# protoBoardLogic.net
KiCad netlist of a schematic drawn in EAGLE
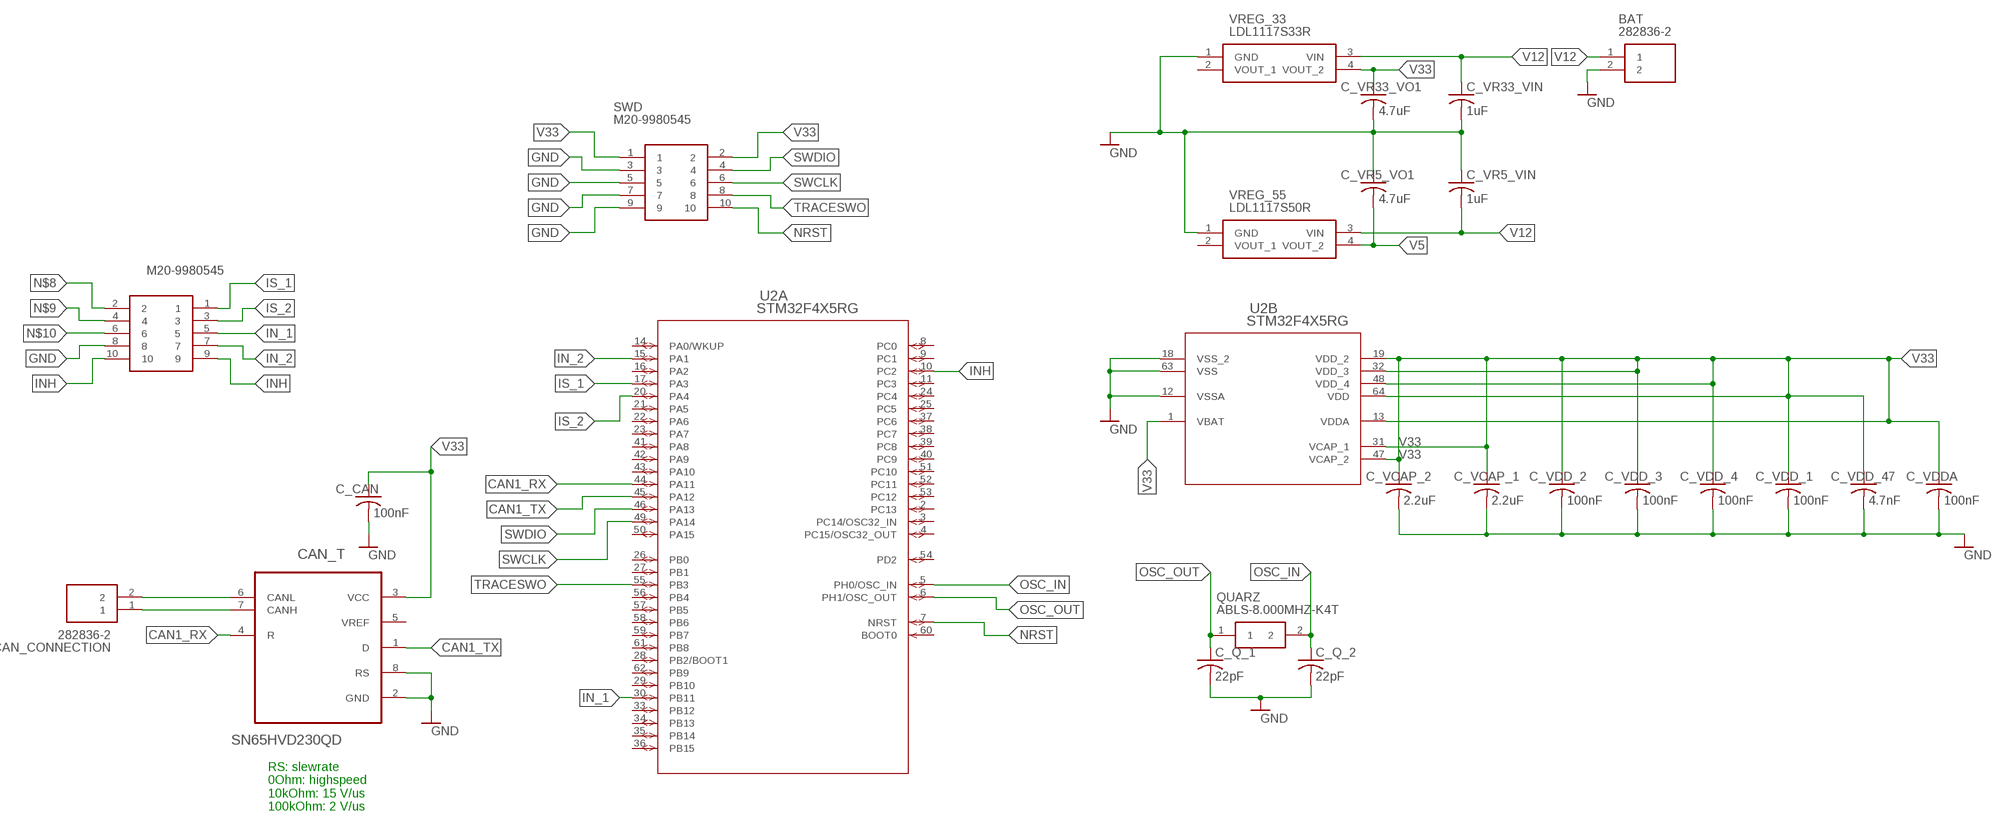
[diagram p0: schematic, sheet 1]

(export (version "E")
  (design (tool "Eeschema 10.0.6"))
  (components
    (comp (ref "BAT")
      (value "282836-2")
      (footprint "eagle-import:SHDR2W100P0X500_1X2_1000X820X1")
      (fields (field (name "MOUSER_PART_NUMBER") "571-2828362"))
      (libsource (lib "eagle-import") (part "282836-2"))
    )
    (comp (ref "CAN_CONNECTION")
      (value "282836-2")
      (footprint "eagle-import:SHDR2W100P0X500_1X2_1000X820X1")
      (fields (field (name "MOUSER_PART_NUMBER") "571-2828362"))
      (libsource (lib "eagle-import") (part "282836-2"))
    )
    (comp (ref "CAN_T")
      (value "SN65HVD230QD")
      (footprint "eagle-import:SOIC127P600X175-8N")
      (fields (field (name "MF") "TEXAS INSTRUMENTS") (field (name "MPN") "SN65HVD230QD.."))
      (libsource (lib "eagle-import") (part "SN65HVD230QD"))
    )
    (comp (ref "C_CAN")
      (value "100nF")
      (footprint "eagle-import:C1206")
      (libsource (lib "eagle-import") (part "C-USC1206"))
    )
    (comp (ref "C_Q_1")
      (value "22pF")
      (footprint "eagle-import:C0805")
      (libsource (lib "eagle-import") (part "C-USC0805"))
    )
    (comp (ref "C_Q_2")
      (value "22pF")
      (footprint "eagle-import:C0805")
      (libsource (lib "eagle-import") (part "C-USC0805"))
    )
    (comp (ref "C_VCAP_1")
      (value "2.2uF")
      (footprint "eagle-import:C1206")
      (libsource (lib "eagle-import") (part "C-USC1206"))
    )
    (comp (ref "C_VCAP_2")
      (value "2.2uF")
      (footprint "eagle-import:C1206")
      (libsource (lib "eagle-import") (part "C-USC1206"))
    )
    (comp (ref "C_VDDA")
      (value "100nF")
      (footprint "eagle-import:C1206")
      (libsource (lib "eagle-import") (part "C-USC1206"))
    )
    (comp (ref "C_VDD_1")
      (value "100nF")
      (footprint "eagle-import:C1206")
      (libsource (lib "eagle-import") (part "C-USC1206"))
    )
    (comp (ref "C_VDD_2")
      (value "100nF")
      (footprint "eagle-import:C1206")
      (libsource (lib "eagle-import") (part "C-USC1206"))
    )
    (comp (ref "C_VDD_3")
      (value "100nF")
      (footprint "eagle-import:C1206")
      (libsource (lib "eagle-import") (part "C-USC1206"))
    )
    (comp (ref "C_VDD_4")
      (value "100nF")
      (footprint "eagle-import:C1206")
      (libsource (lib "eagle-import") (part "C-USC1206"))
    )
    (comp (ref "C_VDD_47")
      (value "4.7nF")
      (footprint "eagle-import:C1206")
      (libsource (lib "eagle-import") (part "C-USC1206"))
    )
    (comp (ref "C_VR5_VIN")
      (value "1uF")
      (footprint "eagle-import:C1206")
      (libsource (lib "eagle-import") (part "C-USC1206"))
    )
    (comp (ref "C_VR5_VO1")
      (value "4.7uF")
      (footprint "eagle-import:C1206")
      (libsource (lib "eagle-import") (part "C-USC1206"))
    )
    (comp (ref "C_VR33_VIN")
      (value "1uF")
      (footprint "eagle-import:C1206")
      (libsource (lib "eagle-import") (part "C-USC1206"))
    )
    (comp (ref "C_VR33_VO1")
      (value "4.7uF")
      (footprint "eagle-import:C1206")
      (libsource (lib "eagle-import") (part "C-USC1206"))
    )
    (comp (ref "HB_ST")
      (value "M20-9980545")
      (footprint "eagle-import:HDRV10W80P254_2X5_1270X508X864")
      (fields (field (name "MOUSER_PART_NUMBER") "855-M20-9980545") (field (name "MF") "HARWIN"))
      (libsource (lib "eagle-import") (part "M20-9980545"))
    )
    (comp (ref "QUARZ")
      (value "ABLS-8.000MHZ-K4T")
      (footprint "eagle-import:ABLS-12.000MHZ-B2")
      (fields (field (name "MOUSER_PART_NUMBER") "815-ABLS-8.0MK4-T") (field (name "MF") "ABRACON"))
      (libsource (lib "eagle-import") (part "ABLS-8.000MHZ-K4T"))
    )
    (comp (ref "SWD")
      (value "M20-9980545")
      (footprint "eagle-import:HDRV10W80P254_2X5_1270X508X864")
      (fields (field (name "MOUSER_PART_NUMBER") "855-M20-9980545") (field (name "MF") "HARWIN"))
      (libsource (lib "eagle-import") (part "M20-9980545"))
    )
    (comp (ref "U2")
      (value "STM32F4X5RG")
      (footprint "eagle-import:LQFP64-10X10MM")
      (fields (field (name "OC_FARNELL") "unknown"))
      (libsource (lib "eagle-import") (part "STM32F4X5RG"))
    )
    (comp (ref "VREG_33")
      (value "LDL1117S33R")
      (footprint "eagle-import:SOT230P700X180-4N")
      (fields (field (name "MOUSER_PART_NUMBER") "511-LDL1117S33R") (field (name "MF") "STMICROELECTRONICS"))
      (libsource (lib "eagle-import") (part "LDL1117S33R"))
    )
    (comp (ref "VREG_55")
      (value "LDL1117S50R")
      (footprint "eagle-import:SOT230P700X180-4N")
      (fields (field (name "MOUSER_PART_NUMBER") "511-LDL1117S50R") (field (name "MF") "STMICROELECTRONICS"))
      (libsource (lib "eagle-import") (part "LDL1117S50R"))
    )
  )
  (nets
    (net (code "1") (name "CAN1_RX") (class "Default")
      (node (ref "CAN_T") (pin "4") (pinfunction "R_4") (pintype "output"))
      (node (ref "U2") (pin "44") (pinfunction "PA11_44") (pintype "bidirectional"))
    )
    (net (code "2") (name "CAN1_TX") (class "Default")
      (node (ref "CAN_T") (pin "1") (pinfunction "D_1") (pintype "input"))
      (node (ref "U2") (pin "45") (pinfunction "PA12_45") (pintype "bidirectional"))
    )
    (net (code "3") (name "GND") (class "Default")
      (node (ref "BAT") (pin "2") (pinfunction "2_2") (pintype "bidirectional"))
      (node (ref "CAN_T") (pin "2") (pinfunction "GND_2") (pintype "passive"))
      (node (ref "CAN_T") (pin "8") (pinfunction "RS_8") (pintype "input"))
      (node (ref "C_CAN") (pin "2") (pinfunction "2_2") (pintype "passive"))
      (node (ref "C_Q_1") (pin "2") (pinfunction "2_2") (pintype "passive"))
      (node (ref "C_Q_2") (pin "2") (pinfunction "2_2") (pintype "passive"))
      (node (ref "C_VCAP_1") (pin "2") (pinfunction "2_2") (pintype "passive"))
      (node (ref "C_VCAP_2") (pin "2") (pinfunction "2_2") (pintype "passive"))
      (node (ref "C_VDDA") (pin "2") (pinfunction "2_2") (pintype "passive"))
      (node (ref "C_VDD_1") (pin "2") (pinfunction "2_2") (pintype "passive"))
      (node (ref "C_VDD_2") (pin "2") (pinfunction "2_2") (pintype "passive"))
      (node (ref "C_VDD_3") (pin "2") (pinfunction "2_2") (pintype "passive"))
      (node (ref "C_VDD_4") (pin "2") (pinfunction "2_2") (pintype "passive"))
      (node (ref "C_VDD_47") (pin "2") (pinfunction "2_2") (pintype "passive"))
      (node (ref "C_VR33_VIN") (pin "2") (pinfunction "2_2") (pintype "passive"))
      (node (ref "C_VR33_VO1") (pin "2") (pinfunction "2_2") (pintype "passive"))
      (node (ref "C_VR5_VIN") (pin "1") (pinfunction "1_1") (pintype "passive"))
      (node (ref "C_VR5_VO1") (pin "1") (pinfunction "1_1") (pintype "passive"))
      (node (ref "HB_ST") (pin "8") (pinfunction "8_8") (pintype "bidirectional"))
      (node (ref "SWD") (pin "3") (pinfunction "3_3") (pintype "bidirectional"))
      (node (ref "SWD") (pin "5") (pinfunction "5_5") (pintype "bidirectional"))
      (node (ref "SWD") (pin "7") (pinfunction "7_7") (pintype "bidirectional"))
      (node (ref "SWD") (pin "9") (pinfunction "9_9") (pintype "bidirectional"))
      (node (ref "U2") (pin "12") (pinfunction "VSSA_12") (pintype "power_in"))
      (node (ref "U2") (pin "18") (pinfunction "VSS_2_18") (pintype "power_in"))
      (node (ref "U2") (pin "63") (pinfunction "VSS_63") (pintype "power_in"))
      (node (ref "VREG_33") (pin "1") (pinfunction "GND_1") (pintype "power_in"))
      (node (ref "VREG_55") (pin "1") (pinfunction "GND_1") (pintype "bidirectional"))
    )
    (net (code "4") (name "INH") (class "Default")
      (node (ref "HB_ST") (pin "10") (pinfunction "10_10") (pintype "bidirectional"))
      (node (ref "HB_ST") (pin "9") (pinfunction "9_9") (pintype "bidirectional"))
      (node (ref "U2") (pin "10") (pinfunction "PC2_10") (pintype "bidirectional"))
    )
    (net (code "5") (name "IN_1") (class "Default")
      (node (ref "HB_ST") (pin "5") (pinfunction "5_5") (pintype "bidirectional"))
      (node (ref "U2") (pin "30") (pinfunction "PB11_30") (pintype "bidirectional"))
    )
    (net (code "6") (name "IN_2") (class "Default")
      (node (ref "HB_ST") (pin "7") (pinfunction "7_7") (pintype "bidirectional"))
      (node (ref "U2") (pin "15") (pinfunction "PA1_15") (pintype "bidirectional"))
    )
    (net (code "7") (name "IS_1") (class "Default")
      (node (ref "HB_ST") (pin "1") (pinfunction "1_1") (pintype "bidirectional"))
      (node (ref "U2") (pin "17") (pinfunction "PA3_17") (pintype "bidirectional"))
    )
    (net (code "8") (name "IS_2") (class "Default")
      (node (ref "HB_ST") (pin "3") (pinfunction "3_3") (pintype "bidirectional"))
      (node (ref "U2") (pin "20") (pinfunction "PA4_20") (pintype "bidirectional"))
    )
    (net (code "9") (name "N$8") (class "Default")
      (node (ref "HB_ST") (pin "2") (pinfunction "2_2") (pintype "bidirectional"))
    )
    (net (code "10") (name "N$9") (class "Default")
      (node (ref "HB_ST") (pin "4") (pinfunction "4_4") (pintype "bidirectional"))
    )
    (net (code "11") (name "N$10") (class "Default")
      (node (ref "HB_ST") (pin "6") (pinfunction "6_6") (pintype "bidirectional"))
    )
    (net (code "12") (name "NRST") (class "Default")
      (node (ref "SWD") (pin "10") (pinfunction "10_10") (pintype "bidirectional"))
      (node (ref "U2") (pin "7") (pinfunction "NRST_7") (pintype "bidirectional"))
    )
    (net (code "13") (name "Net-(CAN_T-CANH)") (class "Default")
      (node (ref "CAN_CONNECTION") (pin "1") (pinfunction "1_1") (pintype "bidirectional"))
      (node (ref "CAN_T") (pin "7") (pinfunction "CANH_7") (pintype "output"))
    )
    (net (code "14") (name "Net-(CAN_T-CANL)") (class "Default")
      (node (ref "CAN_CONNECTION") (pin "2") (pinfunction "2_2") (pintype "bidirectional"))
      (node (ref "CAN_T") (pin "6") (pinfunction "CANL_6") (pintype "output"))
    )
    (net (code "15") (name "OSC_IN") (class "Default")
      (node (ref "C_Q_2") (pin "1") (pinfunction "1_1") (pintype "passive"))
      (node (ref "QUARZ") (pin "2") (pinfunction "2_2") (pintype "bidirectional"))
      (node (ref "U2") (pin "5") (pinfunction "PH0/OSC_IN_5") (pintype "bidirectional"))
    )
    (net (code "16") (name "OSC_OUT") (class "Default")
      (node (ref "C_Q_1") (pin "1") (pinfunction "1_1") (pintype "passive"))
      (node (ref "QUARZ") (pin "1") (pinfunction "1_1") (pintype "bidirectional"))
      (node (ref "U2") (pin "6") (pinfunction "PH1/OSC_OUT_6") (pintype "bidirectional"))
    )
    (net (code "17") (name "SWCLK") (class "Default")
      (node (ref "SWD") (pin "6") (pinfunction "6_6") (pintype "bidirectional"))
      (node (ref "U2") (pin "49") (pinfunction "PA14_49") (pintype "bidirectional"))
    )
    (net (code "18") (name "SWDIO") (class "Default")
      (node (ref "SWD") (pin "4") (pinfunction "4_4") (pintype "bidirectional"))
      (node (ref "U2") (pin "46") (pinfunction "PA13_46") (pintype "bidirectional"))
    )
    (net (code "19") (name "TRACESWO") (class "Default")
      (node (ref "SWD") (pin "8") (pinfunction "8_8") (pintype "bidirectional"))
      (node (ref "U2") (pin "55") (pinfunction "PB3_55") (pintype "bidirectional"))
    )
    (net (code "20") (name "V5") (class "Default")
      (node (ref "C_VR5_VO1") (pin "2") (pinfunction "2_2") (pintype "passive"))
      (node (ref "VREG_55") (pin "4") (pinfunction "VOUT_2_4") (pintype "bidirectional"))
    )
    (net (code "21") (name "V12") (class "Default")
      (node (ref "BAT") (pin "1") (pinfunction "1_1") (pintype "bidirectional"))
      (node (ref "C_VR33_VIN") (pin "1") (pinfunction "1_1") (pintype "passive"))
      (node (ref "C_VR5_VIN") (pin "2") (pinfunction "2_2") (pintype "passive"))
      (node (ref "VREG_33") (pin "3") (pinfunction "VIN_3") (pintype "input"))
      (node (ref "VREG_55") (pin "3") (pinfunction "VIN_3") (pintype "bidirectional"))
    )
    (net (code "22") (name "V33") (class "Default")
      (node (ref "CAN_T") (pin "3") (pinfunction "VCC_3") (pintype "power_in"))
      (node (ref "C_CAN") (pin "1") (pinfunction "1_1") (pintype "passive"))
      (node (ref "C_VCAP_1") (pin "1") (pinfunction "1_1") (pintype "passive"))
      (node (ref "C_VCAP_2") (pin "1") (pinfunction "1_1") (pintype "passive"))
      (node (ref "C_VDDA") (pin "1") (pinfunction "1_1") (pintype "passive"))
      (node (ref "C_VDD_1") (pin "1") (pinfunction "1_1") (pintype "passive"))
      (node (ref "C_VDD_2") (pin "1") (pinfunction "1_1") (pintype "passive"))
      (node (ref "C_VDD_3") (pin "1") (pinfunction "1_1") (pintype "passive"))
      (node (ref "C_VDD_4") (pin "1") (pinfunction "1_1") (pintype "passive"))
      (node (ref "C_VDD_47") (pin "1") (pinfunction "1_1") (pintype "passive"))
      (node (ref "C_VR33_VO1") (pin "1") (pinfunction "1_1") (pintype "passive"))
      (node (ref "SWD") (pin "1") (pinfunction "1_1") (pintype "bidirectional"))
      (node (ref "SWD") (pin "2") (pinfunction "2_2") (pintype "bidirectional"))
      (node (ref "U2") (pin "1") (pinfunction "VBAT_1") (pintype "power_in"))
      (node (ref "U2") (pin "13") (pinfunction "VDDA_13") (pintype "power_in"))
      (node (ref "U2") (pin "19") (pinfunction "VDD_2_19") (pintype "power_in"))
      (node (ref "U2") (pin "31") (pinfunction "VCAP_1_31") (pintype "power_in"))
      (node (ref "U2") (pin "32") (pinfunction "VDD_3_32") (pintype "power_in"))
      (node (ref "U2") (pin "47") (pinfunction "VCAP_2_47") (pintype "power_in"))
      (node (ref "U2") (pin "48") (pinfunction "VDD_4_48") (pintype "power_in"))
      (node (ref "U2") (pin "64") (pinfunction "VDD_64") (pintype "power_in"))
      (node (ref "VREG_33") (pin "4") (pinfunction "VOUT_2_4") (pintype "output"))
    )
    (net (code "23") (name "unconnected-(CAN_T-VREF-Pad5)") (class "Default")
      (node (ref "CAN_T") (pin "5") (pinfunction "VREF_5") (pintype "input"))
    )
    (net (code "24") (name "unconnected-(U2A-BOOT0-Pad60)") (class "Default")
      (node (ref "U2") (pin "60") (pinfunction "BOOT0_60") (pintype "input"))
    )
    (net (code "25") (name "unconnected-(U2A-PA0{slash}WKUP-Pad14)") (class "Default")
      (node (ref "U2") (pin "14") (pinfunction "PA0/WKUP_14") (pintype "bidirectional"))
    )
    (net (code "26") (name "unconnected-(U2A-PA2-Pad16)") (class "Default")
      (node (ref "U2") (pin "16") (pinfunction "PA2_16") (pintype "bidirectional"))
    )
    (net (code "27") (name "unconnected-(U2A-PA5-Pad21)") (class "Default")
      (node (ref "U2") (pin "21") (pinfunction "PA5_21") (pintype "bidirectional"))
    )
    (net (code "28") (name "unconnected-(U2A-PA6-Pad22)") (class "Default")
      (node (ref "U2") (pin "22") (pinfunction "PA6_22") (pintype "bidirectional"))
    )
    (net (code "29") (name "unconnected-(U2A-PA7-Pad23)") (class "Default")
      (node (ref "U2") (pin "23") (pinfunction "PA7_23") (pintype "bidirectional"))
    )
    (net (code "30") (name "unconnected-(U2A-PA8-Pad41)") (class "Default")
      (node (ref "U2") (pin "41") (pinfunction "PA8_41") (pintype "bidirectional"))
    )
    (net (code "31") (name "unconnected-(U2A-PA9-Pad42)") (class "Default")
      (node (ref "U2") (pin "42") (pinfunction "PA9_42") (pintype "bidirectional"))
    )
    (net (code "32") (name "unconnected-(U2A-PA10-Pad43)") (class "Default")
      (node (ref "U2") (pin "43") (pinfunction "PA10_43") (pintype "bidirectional"))
    )
    (net (code "33") (name "unconnected-(U2A-PA15-Pad50)") (class "Default")
      (node (ref "U2") (pin "50") (pinfunction "PA15_50") (pintype "bidirectional"))
    )
    (net (code "34") (name "unconnected-(U2A-PB0-Pad26)") (class "Default")
      (node (ref "U2") (pin "26") (pinfunction "PB0_26") (pintype "bidirectional"))
    )
    (net (code "35") (name "unconnected-(U2A-PB1-Pad27)") (class "Default")
      (node (ref "U2") (pin "27") (pinfunction "PB1_27") (pintype "bidirectional"))
    )
    (net (code "36") (name "unconnected-(U2A-PB2{slash}BOOT1-Pad28)") (class "Default")
      (node (ref "U2") (pin "28") (pinfunction "PB2/BOOT1_28") (pintype "bidirectional"))
    )
    (net (code "37") (name "unconnected-(U2A-PB4-Pad56)") (class "Default")
      (node (ref "U2") (pin "56") (pinfunction "PB4_56") (pintype "bidirectional"))
    )
    (net (code "38") (name "unconnected-(U2A-PB5-Pad57)") (class "Default")
      (node (ref "U2") (pin "57") (pinfunction "PB5_57") (pintype "bidirectional"))
    )
    (net (code "39") (name "unconnected-(U2A-PB6-Pad58)") (class "Default")
      (node (ref "U2") (pin "58") (pinfunction "PB6_58") (pintype "bidirectional"))
    )
    (net (code "40") (name "unconnected-(U2A-PB7-Pad59)") (class "Default")
      (node (ref "U2") (pin "59") (pinfunction "PB7_59") (pintype "bidirectional"))
    )
    (net (code "41") (name "unconnected-(U2A-PB8-Pad61)") (class "Default")
      (node (ref "U2") (pin "61") (pinfunction "PB8_61") (pintype "bidirectional"))
    )
    (net (code "42") (name "unconnected-(U2A-PB9-Pad62)") (class "Default")
      (node (ref "U2") (pin "62") (pinfunction "PB9_62") (pintype "bidirectional"))
    )
    (net (code "43") (name "unconnected-(U2A-PB10-Pad29)") (class "Default")
      (node (ref "U2") (pin "29") (pinfunction "PB10_29") (pintype "bidirectional"))
    )
    (net (code "44") (name "unconnected-(U2A-PB12-Pad33)") (class "Default")
      (node (ref "U2") (pin "33") (pinfunction "PB12_33") (pintype "bidirectional"))
    )
    (net (code "45") (name "unconnected-(U2A-PB13-Pad34)") (class "Default")
      (node (ref "U2") (pin "34") (pinfunction "PB13_34") (pintype "bidirectional"))
    )
    (net (code "46") (name "unconnected-(U2A-PB14-Pad35)") (class "Default")
      (node (ref "U2") (pin "35") (pinfunction "PB14_35") (pintype "bidirectional"))
    )
    (net (code "47") (name "unconnected-(U2A-PB15-Pad36)") (class "Default")
      (node (ref "U2") (pin "36") (pinfunction "PB15_36") (pintype "bidirectional"))
    )
    (net (code "48") (name "unconnected-(U2A-PC0-Pad8)") (class "Default")
      (node (ref "U2") (pin "8") (pinfunction "PC0_8") (pintype "bidirectional"))
    )
    (net (code "49") (name "unconnected-(U2A-PC1-Pad9)") (class "Default")
      (node (ref "U2") (pin "9") (pinfunction "PC1_9") (pintype "bidirectional"))
    )
    (net (code "50") (name "unconnected-(U2A-PC3-Pad11)") (class "Default")
      (node (ref "U2") (pin "11") (pinfunction "PC3_11") (pintype "bidirectional"))
    )
    (net (code "51") (name "unconnected-(U2A-PC4-Pad24)") (class "Default")
      (node (ref "U2") (pin "24") (pinfunction "PC4_24") (pintype "bidirectional"))
    )
    (net (code "52") (name "unconnected-(U2A-PC5-Pad25)") (class "Default")
      (node (ref "U2") (pin "25") (pinfunction "PC5_25") (pintype "bidirectional"))
    )
    (net (code "53") (name "unconnected-(U2A-PC6-Pad37)") (class "Default")
      (node (ref "U2") (pin "37") (pinfunction "PC6_37") (pintype "bidirectional"))
    )
    (net (code "54") (name "unconnected-(U2A-PC7-Pad38)") (class "Default")
      (node (ref "U2") (pin "38") (pinfunction "PC7_38") (pintype "bidirectional"))
    )
    (net (code "55") (name "unconnected-(U2A-PC8-Pad39)") (class "Default")
      (node (ref "U2") (pin "39") (pinfunction "PC8_39") (pintype "bidirectional"))
    )
    (net (code "56") (name "unconnected-(U2A-PC9-Pad40)") (class "Default")
      (node (ref "U2") (pin "40") (pinfunction "PC9_40") (pintype "bidirectional"))
    )
    (net (code "57") (name "unconnected-(U2A-PC10-Pad51)") (class "Default")
      (node (ref "U2") (pin "51") (pinfunction "PC10_51") (pintype "bidirectional"))
    )
    (net (code "58") (name "unconnected-(U2A-PC11-Pad52)") (class "Default")
      (node (ref "U2") (pin "52") (pinfunction "PC11_52") (pintype "bidirectional"))
    )
    (net (code "59") (name "unconnected-(U2A-PC12-Pad53)") (class "Default")
      (node (ref "U2") (pin "53") (pinfunction "PC12_53") (pintype "bidirectional"))
    )
    (net (code "60") (name "unconnected-(U2A-PC13-Pad2)") (class "Default")
      (node (ref "U2") (pin "2") (pinfunction "PC13_2") (pintype "bidirectional"))
    )
    (net (code "61") (name "unconnected-(U2A-PC14{slash}OSC32_IN-Pad3)") (class "Default")
      (node (ref "U2") (pin "3") (pinfunction "PC14/OSC32_IN_3") (pintype "bidirectional"))
    )
    (net (code "62") (name "unconnected-(U2A-PC15{slash}OSC32_OUT-Pad4)") (class "Default")
      (node (ref "U2") (pin "4") (pinfunction "PC15/OSC32_OUT_4") (pintype "bidirectional"))
    )
    (net (code "63") (name "unconnected-(U2A-PD2-Pad54)") (class "Default")
      (node (ref "U2") (pin "54") (pinfunction "PD2_54") (pintype "bidirectional"))
    )
    (net (code "64") (name "unconnected-(VREG_33-VOUT_1-Pad2)") (class "Default")
      (node (ref "VREG_33") (pin "2") (pinfunction "VOUT_1_2") (pintype "output"))
    )
    (net (code "65") (name "unconnected-(VREG_55-VOUT_1-Pad2)") (class "Default")
      (node (ref "VREG_55") (pin "2") (pinfunction "VOUT_1_2") (pintype "bidirectional"))
    )
  )
)
